# MCP73831T-5ACI.net
KiCad netlist of a schematic drawn in Altium Designer
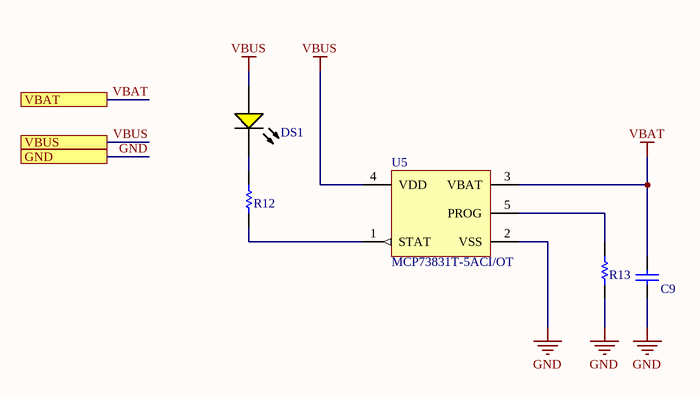
[diagram p0: MCP73831T-5ACI.SchDoc]

(export (version "E")
  (design (tool "Eeschema 10.0.6"))
  (components
    (comp (ref "C9")
      (value "C0805C106K4PACTU")
      (footprint "CAPC2013X140X50NL20T25")
      (description "10µF ±10% 16V Ceramic Capacitor X5R 0805 (2012 Metric)")
      (fields (field (name "PART NUMBER") "CL21A106KOQNNNG"))
      (libsource (lib "Altium Content Vault") (part "CAP"))
    )
    (comp (ref "DS1")
      (value "LTST-C150KSKT")
      (footprint "LTST-C150KSKT_V")
      (description "LED Yellow, 75 mW, 80 mA, -55 to 85 degC, 2-Pin SMD, RoHS, Tape and Reel")
      (fields (field (name "MANUFACTURER") "Lite-On"))
      (libsource (lib "Altium Content Vault") (part "LED-YELLOW-AK-2"))
    )
    (comp (ref "R12")
      (value "ERJ-P06J102V")
      (footprint "RESC2013X70X40NL20T20")
      (description "RES SMD 1K OHM 5% 1/2W 0805")
      (fields (field (name "MANUFACTURER") "Panasonic"))
      (libsource (lib "Altium Content Vault") (part "RES"))
    )
    (comp (ref "R13")
      (value "RC0805JR-074K7L")
      (footprint "RESC2013X60X30NL20T20")
      (description "4.7 kOhms ±5% 0.125W, 1/8W Chip Resistor 0805 (2012 Metric) Moisture Resistant Thick Film")
      (fields (field (name "MANUFACTURER") "Yageo"))
      (libsource (lib "LIB_FIT") (part "RC0805JR-074K7L"))
    )
    (comp (ref "U5")
      (value "MCP73831T-5ACI/OT")
      (footprint "SOT-23-OT5_N")
      (libsource (lib "Altium Content Vault") (part "PM-BM-MCP73831-SOT5"))
    )
  )
  (nets
    (net (code "1") (name "GND") (class "Default")
      (node (ref "C9") (pin "2") (pinfunction "2_2") (pintype "passive"))
      (node (ref "R13") (pin "2") (pinfunction "2_2") (pintype "passive"))
      (node (ref "U5") (pin "2") (pinfunction "VSS_2") (pintype "power_in"))
    )
    (net (code "2") (name "Net-(DS1-K)") (class "Default")
      (node (ref "DS1") (pin "2") (pinfunction "K_2") (pintype "passive"))
      (node (ref "R12") (pin "2") (pinfunction "2_2") (pintype "passive"))
    )
    (net (code "3") (name "Net-(U5-PROG)") (class "Default")
      (node (ref "R13") (pin "1") (pinfunction "1_1") (pintype "passive"))
      (node (ref "U5") (pin "5") (pinfunction "PROG_5") (pintype "passive"))
    )
    (net (code "4") (name "Net-(U5-STAT)") (class "Default")
      (node (ref "R12") (pin "1") (pinfunction "1_1") (pintype "passive"))
      (node (ref "U5") (pin "1") (pinfunction "STAT_1") (pintype "output"))
    )
    (net (code "5") (name "VBAT") (class "Default")
      (node (ref "C9") (pin "1") (pinfunction "1_1") (pintype "passive"))
      (node (ref "U5") (pin "3") (pinfunction "VBAT_3") (pintype "power_in"))
    )
    (net (code "6") (name "VBUS") (class "Default")
      (node (ref "DS1") (pin "1") (pinfunction "A_1") (pintype "passive"))
      (node (ref "U5") (pin "4") (pinfunction "VDD_4") (pintype "power_in"))
    )
  )
)
